# Blanket_Diagram.net
KiCad netlist of a schematic drawn in EAGLE
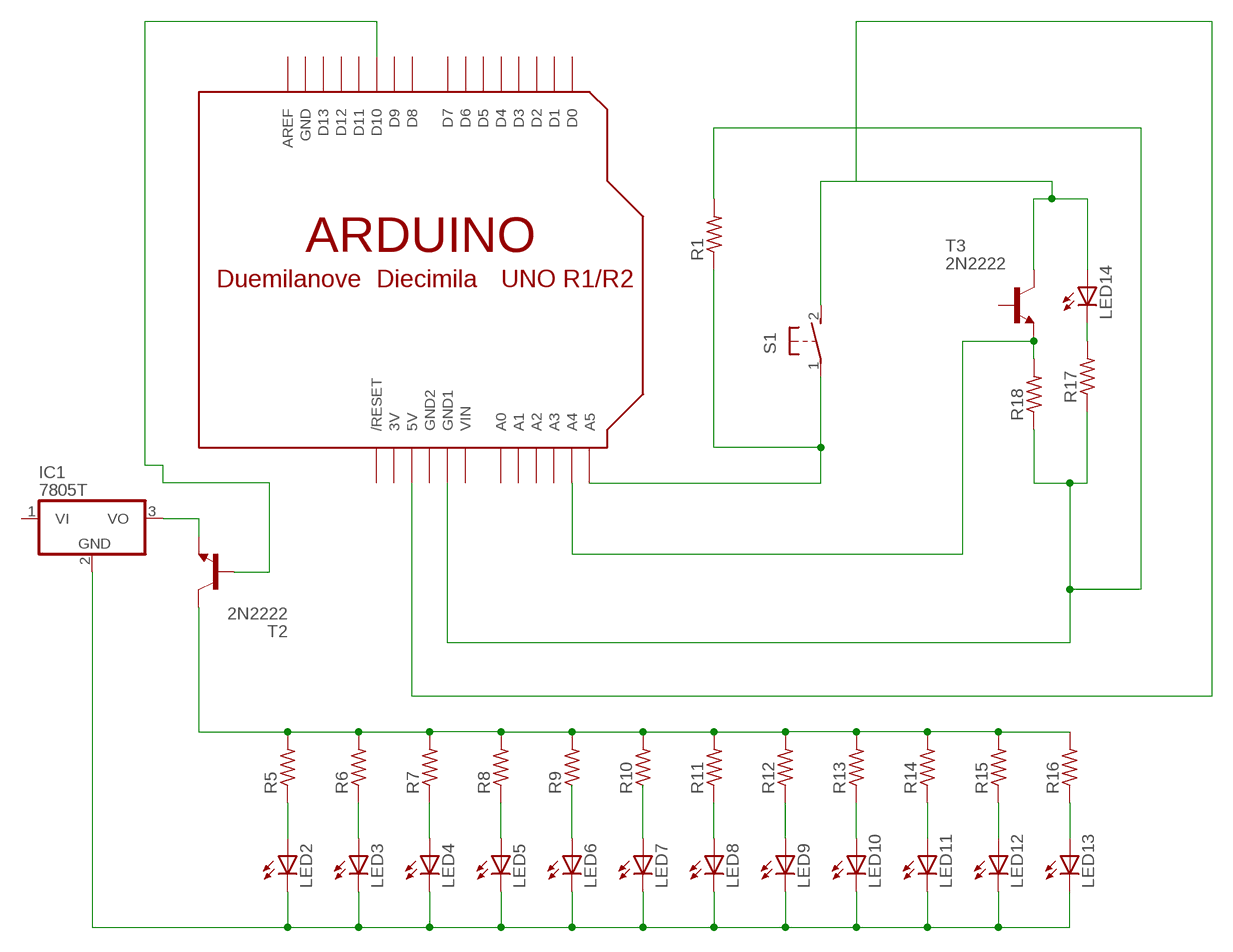
[diagram p0: schematic, sheet 1]

(export (version "E")
  (design (tool "Eeschema 10.0.6"))
  (components
    (comp (ref "IC1")
      (value "7805T")
      (footprint "eagle-import:TO220H")
      (libsource (lib "eagle-import") (part "78T05"))
    )
    (comp (ref "LED2")
      (value "LEDLD260")
      (footprint "eagle-import:LD260")
      (libsource (lib "eagle-import") (part "LEDLD260"))
    )
    (comp (ref "LED3")
      (value "LEDLD260")
      (footprint "eagle-import:LD260")
      (libsource (lib "eagle-import") (part "LEDLD260"))
    )
    (comp (ref "LED4")
      (value "LEDLD260")
      (footprint "eagle-import:LD260")
      (libsource (lib "eagle-import") (part "LEDLD260"))
    )
    (comp (ref "LED5")
      (value "LEDLD260")
      (footprint "eagle-import:LD260")
      (libsource (lib "eagle-import") (part "LEDLD260"))
    )
    (comp (ref "LED6")
      (value "LEDLD260")
      (footprint "eagle-import:LD260")
      (libsource (lib "eagle-import") (part "LEDLD260"))
    )
    (comp (ref "LED7")
      (value "LEDLD260")
      (footprint "eagle-import:LD260")
      (libsource (lib "eagle-import") (part "LEDLD260"))
    )
    (comp (ref "LED8")
      (value "LEDLD260")
      (footprint "eagle-import:LD260")
      (libsource (lib "eagle-import") (part "LEDLD260"))
    )
    (comp (ref "LED9")
      (value "LEDLD260")
      (footprint "eagle-import:LD260")
      (libsource (lib "eagle-import") (part "LEDLD260"))
    )
    (comp (ref "LED10")
      (value "LEDLD260")
      (footprint "eagle-import:LD260")
      (libsource (lib "eagle-import") (part "LEDLD260"))
    )
    (comp (ref "LED11")
      (value "LEDLD260")
      (footprint "eagle-import:LD260")
      (libsource (lib "eagle-import") (part "LEDLD260"))
    )
    (comp (ref "LED12")
      (value "LEDLD260")
      (footprint "eagle-import:LD260")
      (libsource (lib "eagle-import") (part "LEDLD260"))
    )
    (comp (ref "LED13")
      (value "LEDLD260")
      (footprint "eagle-import:LD260")
      (libsource (lib "eagle-import") (part "LEDLD260"))
    )
    (comp (ref "LED14")
      (value "LED")
      (footprint "eagle-import:SMARTLED-TTW")
      (libsource (lib "eagle-import") (part "LED"))
    )
    (comp (ref "R1")
      (value "R-US_0204/7")
      (footprint "eagle-import:0204_7")
      (libsource (lib "eagle-import") (part "R-US_0204/7"))
    )
    (comp (ref "R5")
      (value "R-US_0204/5")
      (footprint "eagle-import:0204_5")
      (libsource (lib "eagle-import") (part "R-US_0204/5"))
    )
    (comp (ref "R6")
      (value "R-US_0204/5")
      (footprint "eagle-import:0204_5")
      (libsource (lib "eagle-import") (part "R-US_0204/5"))
    )
    (comp (ref "R7")
      (value "R-US_0204/5")
      (footprint "eagle-import:0204_5")
      (libsource (lib "eagle-import") (part "R-US_0204/5"))
    )
    (comp (ref "R8")
      (value "R-US_0204/5")
      (footprint "eagle-import:0204_5")
      (libsource (lib "eagle-import") (part "R-US_0204/5"))
    )
    (comp (ref "R9")
      (value "R-US_0204/5")
      (footprint "eagle-import:0204_5")
      (libsource (lib "eagle-import") (part "R-US_0204/5"))
    )
    (comp (ref "R10")
      (value "R-US_0204/5")
      (footprint "eagle-import:0204_5")
      (libsource (lib "eagle-import") (part "R-US_0204/5"))
    )
    (comp (ref "R11")
      (value "R-US_0204/5")
      (footprint "eagle-import:0204_5")
      (libsource (lib "eagle-import") (part "R-US_0204/5"))
    )
    (comp (ref "R12")
      (value "R-US_0204/5")
      (footprint "eagle-import:0204_5")
      (libsource (lib "eagle-import") (part "R-US_0204/5"))
    )
    (comp (ref "R13")
      (value "R-US_0204/5")
      (footprint "eagle-import:0204_5")
      (libsource (lib "eagle-import") (part "R-US_0204/5"))
    )
    (comp (ref "R14")
      (value "R-US_0204/5")
      (footprint "eagle-import:0204_5")
      (libsource (lib "eagle-import") (part "R-US_0204/5"))
    )
    (comp (ref "R15")
      (value "R-US_0204/5")
      (footprint "eagle-import:0204_5")
      (libsource (lib "eagle-import") (part "R-US_0204/5"))
    )
    (comp (ref "R16")
      (value "R-US_0204/5")
      (footprint "eagle-import:0204_5")
      (libsource (lib "eagle-import") (part "R-US_0204/5"))
    )
    (comp (ref "R17")
      (value "R-US_0204/7")
      (footprint "eagle-import:0204_7")
      (libsource (lib "eagle-import") (part "R-US_0204/7"))
    )
    (comp (ref "R18")
      (value "R-US_0204/7")
      (footprint "eagle-import:0204_7")
      (libsource (lib "eagle-import") (part "R-US_0204/7"))
    )
    (comp (ref "S1")
      (value "31-XX")
      (footprint "eagle-import:B3F-31XX")
      (libsource (lib "eagle-import") (part "31-XX"))
    )
    (comp (ref "T2")
      (value "2N2222")
      (footprint "eagle-import:TO92-EBC-OVAL")
      (libsource (lib "eagle-import") (part "2N2222"))
    )
    (comp (ref "T3")
      (value "2N2222")
      (footprint "eagle-import:TO92-EBC-OVAL")
      (libsource (lib "eagle-import") (part "2N2222"))
    )
    (comp (ref "U$1")
      (value "ARDUINOUNO")
      (footprint "eagle-import:ARDUINO")
      (libsource (lib "eagle-import") (part "ARDUINOUNO"))
    )
  )
  (nets
    (net (code "1") (name "/3V") (class "Default")
      (node (ref "U$1") (pin "3V") (pinfunction "3V_3V") (pintype "power_in"))
    )
    (net (code "2") (name "/GND") (class "Default")
      (node (ref "U$1") (pin "GND") (pinfunction "GND_GND") (pintype "power_in"))
    )
    (net (code "3") (name "/GND2") (class "Default")
      (node (ref "U$1") (pin "GND2") (pinfunction "GND2_GND2") (pintype "power_in"))
    )
    (net (code "4") (name "/VIN") (class "Default")
      (node (ref "U$1") (pin "VIN") (pinfunction "VIN_VIN") (pintype "power_in"))
    )
    (net (code "5") (name "Net-(IC1-GND)") (class "Default")
      (node (ref "IC1") (pin "2") (pinfunction "GND_2") (pintype "passive"))
      (node (ref "LED10") (pin "K") (pinfunction "C_K") (pintype "passive"))
      (node (ref "LED11") (pin "K") (pinfunction "C_K") (pintype "passive"))
      (node (ref "LED12") (pin "K") (pinfunction "C_K") (pintype "passive"))
      (node (ref "LED13") (pin "K") (pinfunction "C_K") (pintype "passive"))
      (node (ref "LED2") (pin "K") (pinfunction "C_K") (pintype "passive"))
      (node (ref "LED3") (pin "K") (pinfunction "C_K") (pintype "passive"))
      (node (ref "LED4") (pin "K") (pinfunction "C_K") (pintype "passive"))
      (node (ref "LED5") (pin "K") (pinfunction "C_K") (pintype "passive"))
      (node (ref "LED6") (pin "K") (pinfunction "C_K") (pintype "passive"))
      (node (ref "LED7") (pin "K") (pinfunction "C_K") (pintype "passive"))
      (node (ref "LED8") (pin "K") (pinfunction "C_K") (pintype "passive"))
      (node (ref "LED9") (pin "K") (pinfunction "C_K") (pintype "passive"))
    )
    (net (code "6") (name "Net-(IC1-VO)") (class "Default")
      (node (ref "IC1") (pin "3") (pinfunction "VO_3") (pintype "passive"))
      (node (ref "T2") (pin "E") (pinfunction "E_E") (pintype "passive"))
    )
    (net (code "7") (name "Net-(LED2-PadA)") (class "Default")
      (node (ref "LED2") (pin "A") (pinfunction "A_A") (pintype "passive"))
      (node (ref "R5") (pin "1") (pinfunction "1_1") (pintype "passive"))
    )
    (net (code "8") (name "Net-(LED3-PadA)") (class "Default")
      (node (ref "LED3") (pin "A") (pinfunction "A_A") (pintype "passive"))
      (node (ref "R6") (pin "1") (pinfunction "1_1") (pintype "passive"))
    )
    (net (code "9") (name "Net-(LED4-PadA)") (class "Default")
      (node (ref "LED4") (pin "A") (pinfunction "A_A") (pintype "passive"))
      (node (ref "R7") (pin "1") (pinfunction "1_1") (pintype "passive"))
    )
    (net (code "10") (name "Net-(LED5-PadA)") (class "Default")
      (node (ref "LED5") (pin "A") (pinfunction "A_A") (pintype "passive"))
      (node (ref "R8") (pin "1") (pinfunction "1_1") (pintype "passive"))
    )
    (net (code "11") (name "Net-(LED8-PadA)") (class "Default")
      (node (ref "LED8") (pin "A") (pinfunction "A_A") (pintype "passive"))
      (node (ref "R11") (pin "1") (pinfunction "1_1") (pintype "passive"))
    )
    (net (code "12") (name "Net-(LED9-PadA)") (class "Default")
      (node (ref "LED9") (pin "A") (pinfunction "A_A") (pintype "passive"))
      (node (ref "R12") (pin "1") (pinfunction "1_1") (pintype "passive"))
    )
    (net (code "13") (name "Net-(LED10-PadA)") (class "Default")
      (node (ref "LED10") (pin "A") (pinfunction "A_A") (pintype "passive"))
      (node (ref "R13") (pin "1") (pinfunction "1_1") (pintype "passive"))
    )
    (net (code "14") (name "Net-(LED11-PadA)") (class "Default")
      (node (ref "LED11") (pin "A") (pinfunction "A_A") (pintype "passive"))
      (node (ref "R14") (pin "1") (pinfunction "1_1") (pintype "passive"))
    )
    (net (code "15") (name "Net-(LED12-PadA)") (class "Default")
      (node (ref "LED12") (pin "A") (pinfunction "A_A") (pintype "passive"))
      (node (ref "R15") (pin "1") (pinfunction "1_1") (pintype "passive"))
    )
    (net (code "16") (name "Net-(LED13-PadA)") (class "Default")
      (node (ref "LED13") (pin "A") (pinfunction "A_A") (pintype "passive"))
      (node (ref "R16") (pin "1") (pinfunction "1_1") (pintype "passive"))
    )
    (net (code "17") (name "Net-(LED14-A)") (class "Default")
      (node (ref "LED14") (pin "A@1") (pinfunction "A_A@1") (pintype "passive"))
      (node (ref "S1") (pin "2") (pinfunction "S_2") (pintype "passive"))
      (node (ref "T3") (pin "C") (pinfunction "C_C") (pintype "passive"))
      (node (ref "U$1") (pin "5V") (pinfunction "5V_5V") (pintype "power_in"))
    )
    (net (code "18") (name "Net-(LED14-C)") (class "Default")
      (node (ref "LED14") (pin "C@1") (pinfunction "C_C@1") (pintype "passive"))
      (node (ref "R17") (pin "2") (pinfunction "2_2") (pintype "passive"))
    )
    (net (code "19") (name "Net-(R1-Pad2)") (class "Default")
      (node (ref "R1") (pin "2") (pinfunction "2_2") (pintype "passive"))
      (node (ref "R17") (pin "1") (pinfunction "1_1") (pintype "passive"))
      (node (ref "R18") (pin "1") (pinfunction "1_1") (pintype "passive"))
      (node (ref "U$1") (pin "GND1") (pinfunction "GND1_GND1") (pintype "power_in"))
    )
    (net (code "20") (name "Net-(R10-Pad2)") (class "Default")
      (node (ref "R10") (pin "2") (pinfunction "2_2") (pintype "passive"))
      (node (ref "R11") (pin "2") (pinfunction "2_2") (pintype "passive"))
      (node (ref "R12") (pin "2") (pinfunction "2_2") (pintype "passive"))
      (node (ref "R13") (pin "2") (pinfunction "2_2") (pintype "passive"))
      (node (ref "R14") (pin "2") (pinfunction "2_2") (pintype "passive"))
      (node (ref "R15") (pin "2") (pinfunction "2_2") (pintype "passive"))
      (node (ref "R16") (pin "2") (pinfunction "2_2") (pintype "passive"))
      (node (ref "R5") (pin "2") (pinfunction "2_2") (pintype "passive"))
      (node (ref "R6") (pin "2") (pinfunction "2_2") (pintype "passive"))
      (node (ref "R7") (pin "2") (pinfunction "2_2") (pintype "passive"))
      (node (ref "R8") (pin "2") (pinfunction "2_2") (pintype "passive"))
      (node (ref "R9") (pin "2") (pinfunction "2_2") (pintype "passive"))
      (node (ref "T2") (pin "C") (pinfunction "C_C") (pintype "passive"))
    )
    (net (code "21") (name "Net-(R18-Pad2)") (class "Default")
      (node (ref "R18") (pin "2") (pinfunction "2_2") (pintype "passive"))
      (node (ref "T3") (pin "E") (pinfunction "E_E") (pintype "passive"))
      (node (ref "U$1") (pin "A4") (pinfunction "A4_A4") (pintype "bidirectional"))
    )
    (net (code "22") (name "Net-(S1-P)") (class "Default")
      (node (ref "R1") (pin "1") (pinfunction "1_1") (pintype "passive"))
      (node (ref "S1") (pin "1") (pinfunction "P_1") (pintype "passive"))
      (node (ref "U$1") (pin "A5") (pinfunction "A5_A5") (pintype "bidirectional"))
    )
    (net (code "23") (name "Net-(T2-PadB)") (class "Default")
      (node (ref "T2") (pin "B") (pinfunction "B_B") (pintype "passive"))
      (node (ref "U$1") (pin "D10") (pinfunction "D10_D10") (pintype "bidirectional"))
    )
    (net (code "24") (name "unconnected-(IC1-VI-Pad1)") (class "Default")
      (node (ref "IC1") (pin "1") (pinfunction "VI_1") (pintype "input"))
    )
    (net (code "25") (name "unconnected-(LED6-PadA)") (class "Default")
      (node (ref "LED6") (pin "A") (pinfunction "A_A") (pintype "passive"))
    )
    (net (code "26") (name "unconnected-(LED7-PadA)") (class "Default")
      (node (ref "LED7") (pin "A") (pinfunction "A_A") (pintype "passive"))
    )
    (net (code "27") (name "unconnected-(R9-Pad1)") (class "Default")
      (node (ref "R9") (pin "1") (pinfunction "1_1") (pintype "passive"))
    )
    (net (code "28") (name "unconnected-(R10-Pad1)") (class "Default")
      (node (ref "R10") (pin "1") (pinfunction "1_1") (pintype "passive"))
    )
    (net (code "29") (name "unconnected-(T3-PadB)") (class "Default")
      (node (ref "T3") (pin "B") (pinfunction "B_B") (pintype "passive"))
    )
    (net (code "30") (name "unconnected-(U$1-PadA0)") (class "Default")
      (node (ref "U$1") (pin "A0") (pinfunction "A0_A0") (pintype "bidirectional"))
    )
    (net (code "31") (name "unconnected-(U$1-PadA1)") (class "Default")
      (node (ref "U$1") (pin "A1") (pinfunction "A1_A1") (pintype "bidirectional"))
    )
    (net (code "32") (name "unconnected-(U$1-PadA2)") (class "Default")
      (node (ref "U$1") (pin "A2") (pinfunction "A2_A2") (pintype "bidirectional"))
    )
    (net (code "33") (name "unconnected-(U$1-PadA3)") (class "Default")
      (node (ref "U$1") (pin "A3") (pinfunction "A3_A3") (pintype "bidirectional"))
    )
    (net (code "34") (name "unconnected-(U$1-PadAREF)") (class "Default")
      (node (ref "U$1") (pin "AREF") (pinfunction "AREF_AREF") (pintype "bidirectional"))
    )
    (net (code "35") (name "unconnected-(U$1-PadD0)") (class "Default")
      (node (ref "U$1") (pin "D0") (pinfunction "D0_D0") (pintype "bidirectional"))
    )
    (net (code "36") (name "unconnected-(U$1-PadD1)") (class "Default")
      (node (ref "U$1") (pin "D1") (pinfunction "D1_D1") (pintype "bidirectional"))
    )
    (net (code "37") (name "unconnected-(U$1-PadD2)") (class "Default")
      (node (ref "U$1") (pin "D2") (pinfunction "D2_D2") (pintype "bidirectional"))
    )
    (net (code "38") (name "unconnected-(U$1-PadD3)") (class "Default")
      (node (ref "U$1") (pin "D3") (pinfunction "D3_D3") (pintype "bidirectional"))
    )
    (net (code "39") (name "unconnected-(U$1-PadD4)") (class "Default")
      (node (ref "U$1") (pin "D4") (pinfunction "D4_D4") (pintype "bidirectional"))
    )
    (net (code "40") (name "unconnected-(U$1-PadD5)") (class "Default")
      (node (ref "U$1") (pin "D5") (pinfunction "D5_D5") (pintype "bidirectional"))
    )
    (net (code "41") (name "unconnected-(U$1-PadD6)") (class "Default")
      (node (ref "U$1") (pin "D6") (pinfunction "D6_D6") (pintype "bidirectional"))
    )
    (net (code "42") (name "unconnected-(U$1-PadD7)") (class "Default")
      (node (ref "U$1") (pin "D7") (pinfunction "D7_D7") (pintype "bidirectional"))
    )
    (net (code "43") (name "unconnected-(U$1-PadD8)") (class "Default")
      (node (ref "U$1") (pin "D8") (pinfunction "D8_D8") (pintype "bidirectional"))
    )
    (net (code "44") (name "unconnected-(U$1-PadD9)") (class "Default")
      (node (ref "U$1") (pin "D9") (pinfunction "D9_D9") (pintype "bidirectional"))
    )
    (net (code "45") (name "unconnected-(U$1-PadD11)") (class "Default")
      (node (ref "U$1") (pin "D11") (pinfunction "D11_D11") (pintype "bidirectional"))
    )
    (net (code "46") (name "unconnected-(U$1-PadD12)") (class "Default")
      (node (ref "U$1") (pin "D12") (pinfunction "D12_D12") (pintype "bidirectional"))
    )
    (net (code "47") (name "unconnected-(U$1-PadD13)") (class "Default")
      (node (ref "U$1") (pin "D13") (pinfunction "D13_D13") (pintype "bidirectional"))
    )
    (net (code "48") (name "unconnected-(U$1-{slash}RESET-PadRESET)") (class "Default")
      (node (ref "U$1") (pin "RESET") (pinfunction "/RESET_RESET") (pintype "bidirectional"))
    )
  )
)
